# sofi_v7_main.net
KiCad netlist of a schematic drawn in EAGLE
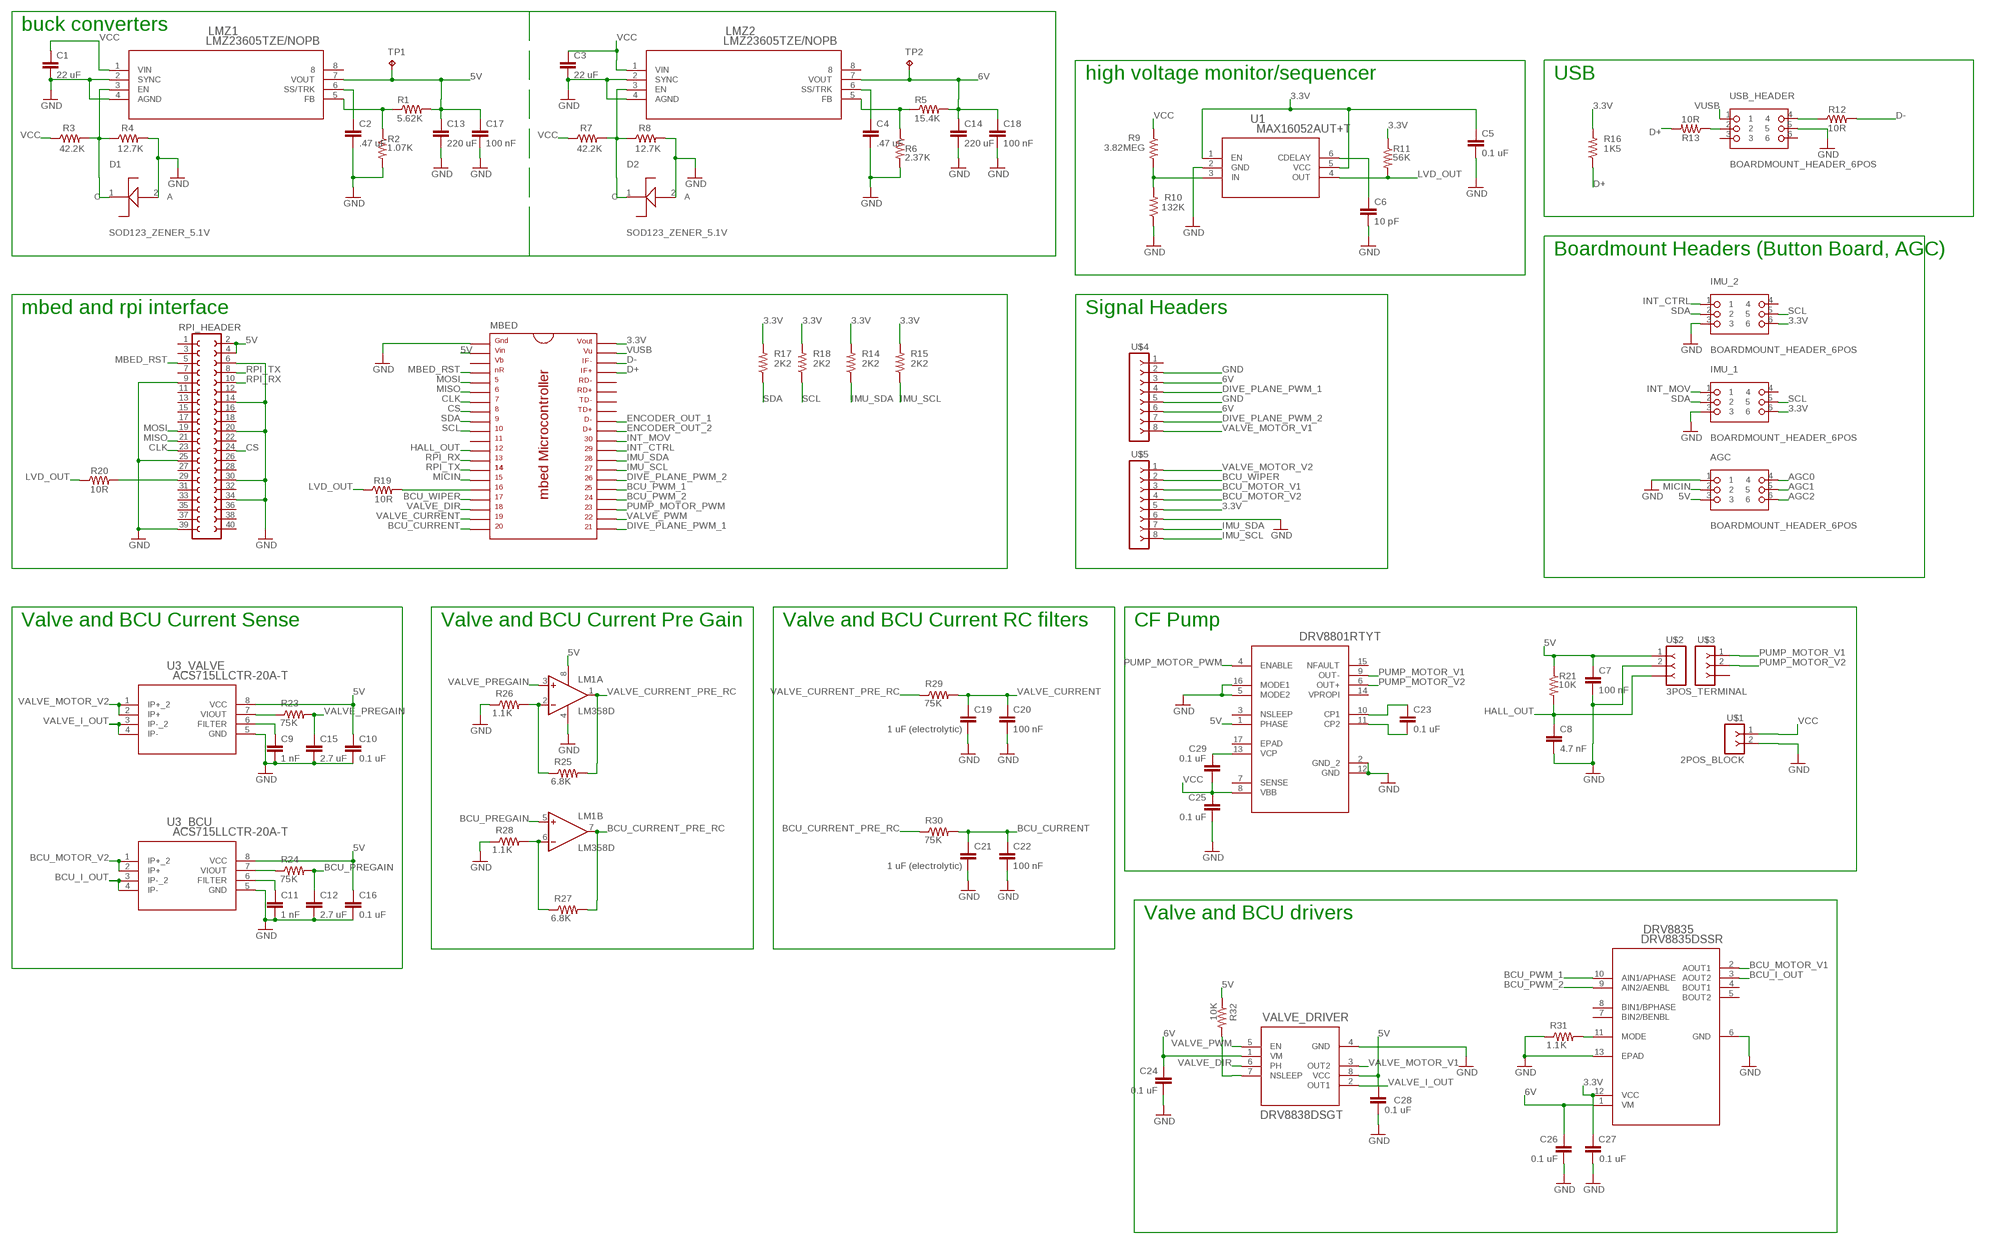
[diagram p0: schematic, sheet 1]

(export (version "E")
  (design (tool "Eeschema 10.0.6"))
  (components
    (comp (ref "AGC")
      (value "BOARDMOUNT_HEADER_6POS")
      (footprint "eagle-import:BOARDMOUNT_HEADER")
      (libsource (lib "eagle-import") (part "BOARDMOUNT_HEADER_6POS"))
    )
    (comp (ref "C1")
      (value "22 uF")
      (footprint "eagle-import:C0805")
      (libsource (lib "eagle-import") (part "C-EUC0805"))
    )
    (comp (ref "C2")
      (value ".47 uF")
      (footprint "eagle-import:C0805")
      (libsource (lib "eagle-import") (part "C-EUC0805"))
    )
    (comp (ref "C3")
      (value "22 uF")
      (footprint "eagle-import:C0805")
      (libsource (lib "eagle-import") (part "C-EUC0805"))
    )
    (comp (ref "C4")
      (value ".47 uF")
      (footprint "eagle-import:C0805")
      (libsource (lib "eagle-import") (part "C-EUC0805"))
    )
    (comp (ref "C5")
      (value "0.1 uF")
      (footprint "eagle-import:C0805")
      (libsource (lib "eagle-import") (part "C-EUC0805"))
    )
    (comp (ref "C6")
      (value "10 pF")
      (footprint "eagle-import:C0603")
      (libsource (lib "eagle-import") (part "C-EUC0603"))
    )
    (comp (ref "C7")
      (value "100 nF")
      (footprint "eagle-import:C0805")
      (libsource (lib "eagle-import") (part "C-EUC0805"))
    )
    (comp (ref "C8")
      (value "4.7 nF")
      (footprint "eagle-import:C0805")
      (libsource (lib "eagle-import") (part "C-EUC0805"))
    )
    (comp (ref "C9")
      (value "1 nF")
      (footprint "eagle-import:C0603")
      (libsource (lib "eagle-import") (part "C-EUC0603"))
    )
    (comp (ref "C10")
      (value "0.1 uF")
      (footprint "eagle-import:C0603")
      (libsource (lib "eagle-import") (part "C-EUC0603"))
    )
    (comp (ref "C11")
      (value "1 nF")
      (footprint "eagle-import:C0603")
      (libsource (lib "eagle-import") (part "C-EUC0603"))
    )
    (comp (ref "C12")
      (value "2.7 uF")
      (footprint "eagle-import:C0603")
      (libsource (lib "eagle-import") (part "C-EUC0603"))
    )
    (comp (ref "C13")
      (value "220 uF")
      (footprint "eagle-import:C1206")
      (libsource (lib "eagle-import") (part "resistor_348_C-EUC1206"))
    )
    (comp (ref "C14")
      (value "220 uF")
      (footprint "eagle-import:C1206")
      (libsource (lib "eagle-import") (part "resistor_348_C-EUC1206"))
    )
    (comp (ref "C15")
      (value "2.7 uF")
      (footprint "eagle-import:C0603")
      (libsource (lib "eagle-import") (part "C-EUC0603"))
    )
    (comp (ref "C16")
      (value "0.1 uF")
      (footprint "eagle-import:C0603")
      (libsource (lib "eagle-import") (part "C-EUC0603"))
    )
    (comp (ref "C17")
      (value "100 nF")
      (footprint "eagle-import:C0805")
      (libsource (lib "eagle-import") (part "C-EUC0805"))
    )
    (comp (ref "C18")
      (value "100 nF")
      (footprint "eagle-import:C0805")
      (libsource (lib "eagle-import") (part "C-EUC0805"))
    )
    (comp (ref "C19")
      (value "1 uF (electrolytic)")
      (footprint "eagle-import:C0603")
      (libsource (lib "eagle-import") (part "C-EUC0603"))
    )
    (comp (ref "C20")
      (value "100 nF")
      (footprint "eagle-import:C0805")
      (libsource (lib "eagle-import") (part "C-EUC0805"))
    )
    (comp (ref "C21")
      (value "1 uF (electrolytic)")
      (footprint "eagle-import:C0603")
      (libsource (lib "eagle-import") (part "C-EUC0603"))
    )
    (comp (ref "C22")
      (value "100 nF")
      (footprint "eagle-import:C0805")
      (libsource (lib "eagle-import") (part "C-EUC0805"))
    )
    (comp (ref "C23")
      (value "0.1 uF")
      (footprint "eagle-import:C0805")
      (libsource (lib "eagle-import") (part "C-EUC0805"))
    )
    (comp (ref "C24")
      (value "0.1 uF")
      (footprint "eagle-import:C0603")
      (libsource (lib "eagle-import") (part "C-EUC0603"))
    )
    (comp (ref "C25")
      (value "0.1 uF")
      (footprint "eagle-import:C0603")
      (libsource (lib "eagle-import") (part "C-EUC0603"))
    )
    (comp (ref "C26")
      (value "0.1 uF")
      (footprint "eagle-import:C0603")
      (libsource (lib "eagle-import") (part "C-EUC0603"))
    )
    (comp (ref "C27")
      (value "0.1 uF")
      (footprint "eagle-import:C0603")
      (libsource (lib "eagle-import") (part "C-EUC0603"))
    )
    (comp (ref "C28")
      (value "0.1 uF")
      (footprint "eagle-import:C0603")
      (libsource (lib "eagle-import") (part "C-EUC0603"))
    )
    (comp (ref "C29")
      (value "0.1 uF")
      (footprint "eagle-import:C0805")
      (libsource (lib "eagle-import") (part "C-EUC0805"))
    )
    (comp (ref "D1")
      (value "SOD123_ZENER_5.1V")
      (footprint "eagle-import:SOD123_ZENER")
      (libsource (lib "eagle-import") (part "SOD123_ZENER_5.1V"))
    )
    (comp (ref "D2")
      (value "SOD123_ZENER_5.1V")
      (footprint "eagle-import:SOD123_ZENER")
      (libsource (lib "eagle-import") (part "SOD123_ZENER_5.1V"))
    )
    (comp (ref "DRV8801")
      (value "DRV8801RTYT")
      (footprint "eagle-import:RTY16")
      (libsource (lib "eagle-import") (part "DRV8801RTYT"))
    )
    (comp (ref "DRV8835")
      (value "DRV8835DSSR")
      (footprint "eagle-import:DSS12_P9X2")
      (libsource (lib "eagle-import") (part "DRV8835DSSR"))
    )
    (comp (ref "IMU_1")
      (value "BOARDMOUNT_HEADER_6POS")
      (footprint "eagle-import:BOARDMOUNT_HEADER")
      (libsource (lib "eagle-import") (part "BOARDMOUNT_HEADER_6POS"))
    )
    (comp (ref "IMU_2")
      (value "BOARDMOUNT_HEADER_6POS")
      (footprint "eagle-import:BOARDMOUNT_HEADER")
      (libsource (lib "eagle-import") (part "BOARDMOUNT_HEADER_6POS"))
    )
    (comp (ref "LM1")
      (value "LM358D")
      (footprint "eagle-import:SO08")
      (libsource (lib "eagle-import") (part "LM358D"))
    )
    (comp (ref "LMZ1")
      (value "LMZ23605TZE/NOPB")
      (footprint "eagle-import:TZA07A")
      (fields (field (name "MANUFACTURER_PART_NUMBER") "LMZ23605TZENOPB"))
      (libsource (lib "eagle-import") (part "LMZ23605TZE/NOPB"))
    )
    (comp (ref "LMZ2")
      (value "LMZ23605TZE/NOPB")
      (footprint "eagle-import:TZA07A")
      (fields (field (name "MANUFACTURER_PART_NUMBER") "LMZ23605TZENOPB"))
      (libsource (lib "eagle-import") (part "LMZ23605TZE/NOPB"))
    )
    (comp (ref "MBED")
      (value "MBED_MICROCONTROLLER")
      (footprint "eagle-import:DIL40_0.9")
      (libsource (lib "eagle-import") (part "MBED_MICROCONTROLLER"))
    )
    (comp (ref "R1")
      (value "5.62K")
      (footprint "eagle-import:M0805")
      (libsource (lib "eagle-import") (part "R-US_M0805"))
    )
    (comp (ref "R2")
      (value "1.07K")
      (footprint "eagle-import:M0805")
      (libsource (lib "eagle-import") (part "R-US_M0805"))
    )
    (comp (ref "R3")
      (value "42.2K")
      (footprint "eagle-import:M0805")
      (libsource (lib "eagle-import") (part "R-US_M0805"))
    )
    (comp (ref "R4")
      (value "12.7K")
      (footprint "eagle-import:M0805")
      (libsource (lib "eagle-import") (part "R-US_M0805"))
    )
    (comp (ref "R5")
      (value "15.4K")
      (footprint "eagle-import:M0805")
      (libsource (lib "eagle-import") (part "R-US_M0805"))
    )
    (comp (ref "R6")
      (value "2.37K")
      (footprint "eagle-import:M0805")
      (libsource (lib "eagle-import") (part "R-US_M0805"))
    )
    (comp (ref "R7")
      (value "42.2K")
      (footprint "eagle-import:M0805")
      (libsource (lib "eagle-import") (part "R-US_M0805"))
    )
    (comp (ref "R8")
      (value "12.7K")
      (footprint "eagle-import:M0805")
      (libsource (lib "eagle-import") (part "R-US_M0805"))
    )
    (comp (ref "R9")
      (value "3.82MEG")
      (footprint "eagle-import:0603")
      (libsource (lib "eagle-import") (part "RESISTOR0603"))
    )
    (comp (ref "R10")
      (value "132K")
      (footprint "eagle-import:0603")
      (libsource (lib "eagle-import") (part "RESISTOR0603"))
    )
    (comp (ref "R11")
      (value "56K")
      (footprint "eagle-import:R0603")
      (libsource (lib "eagle-import") (part "R-US_R0603"))
    )
    (comp (ref "R12")
      (value "10R")
      (footprint "eagle-import:0603")
      (libsource (lib "eagle-import") (part "RESISTOR0603"))
    )
    (comp (ref "R13")
      (value "10R")
      (footprint "eagle-import:0603")
      (libsource (lib "eagle-import") (part "RESISTOR0603"))
    )
    (comp (ref "R14")
      (value "2K2")
      (footprint "eagle-import:0603")
      (libsource (lib "eagle-import") (part "RESISTOR0603"))
    )
    (comp (ref "R15")
      (value "2K2")
      (footprint "eagle-import:0603")
      (libsource (lib "eagle-import") (part "RESISTOR0603"))
    )
    (comp (ref "R16")
      (value "1K5")
      (footprint "eagle-import:0603")
      (libsource (lib "eagle-import") (part "RESISTOR0603"))
    )
    (comp (ref "R17")
      (value "2K2")
      (footprint "eagle-import:0603")
      (libsource (lib "eagle-import") (part "RESISTOR0603"))
    )
    (comp (ref "R18")
      (value "2K2")
      (footprint "eagle-import:0603")
      (libsource (lib "eagle-import") (part "RESISTOR0603"))
    )
    (comp (ref "R19")
      (value "10R")
      (footprint "eagle-import:0603")
      (libsource (lib "eagle-import") (part "RESISTOR0603"))
    )
    (comp (ref "R20")
      (value "10R")
      (footprint "eagle-import:0603")
      (libsource (lib "eagle-import") (part "RESISTOR0603"))
    )
    (comp (ref "R21")
      (value "10K")
      (footprint "eagle-import:M0805")
      (libsource (lib "eagle-import") (part "R-US_M0805"))
    )
    (comp (ref "R23")
      (value "75K")
      (footprint "eagle-import:M0805")
      (libsource (lib "eagle-import") (part "R-US_M0805"))
    )
    (comp (ref "R24")
      (value "75K")
      (footprint "eagle-import:M0805")
      (libsource (lib "eagle-import") (part "R-US_M0805"))
    )
    (comp (ref "R25")
      (value "6.8K")
      (footprint "eagle-import:M0805")
      (libsource (lib "eagle-import") (part "R-US_M0805"))
    )
    (comp (ref "R26")
      (value "1.1K")
      (footprint "eagle-import:M0805")
      (libsource (lib "eagle-import") (part "R-US_M0805"))
    )
    (comp (ref "R27")
      (value "6.8K")
      (footprint "eagle-import:M0805")
      (libsource (lib "eagle-import") (part "R-US_M0805"))
    )
    (comp (ref "R28")
      (value "1.1K")
      (footprint "eagle-import:M0805")
      (libsource (lib "eagle-import") (part "R-US_M0805"))
    )
    (comp (ref "R29")
      (value "75K")
      (footprint "eagle-import:M0805")
      (libsource (lib "eagle-import") (part "R-US_M0805"))
    )
    (comp (ref "R30")
      (value "75K")
      (footprint "eagle-import:M0805")
      (libsource (lib "eagle-import") (part "R-US_M0805"))
    )
    (comp (ref "R31")
      (value "1.1K")
      (footprint "eagle-import:M0805")
      (libsource (lib "eagle-import") (part "R-US_M0805"))
    )
    (comp (ref "R32")
      (value "10K")
      (footprint "eagle-import:M0805")
      (libsource (lib "eagle-import") (part "R-US_M0805"))
    )
    (comp (ref "RPI_HEADER")
      (value "FE20-2")
      (footprint "eagle-import:FE20-2")
      (libsource (lib "eagle-import") (part "FE20-2"))
    )
    (comp (ref "TP1")
      (value "TPB1,27")
      (footprint "eagle-import:B1,27")
      (libsource (lib "eagle-import") (part "TPB1,27"))
    )
    (comp (ref "TP2")
      (value "TPB1,27")
      (footprint "eagle-import:B1,27")
      (libsource (lib "eagle-import") (part "TPB1,27"))
    )
    (comp (ref "U$1")
      (value "2POS_BLOCK")
      (footprint "eagle-import:2POS_BLOCK")
      (libsource (lib "eagle-import") (part "2POS_BLOCK"))
    )
    (comp (ref "U$2")
      (value "3POS_TERMINAL")
      (footprint "eagle-import:3POS_TERMINAL")
      (libsource (lib "eagle-import") (part "3POS_TERMINAL"))
    )
    (comp (ref "U$3")
      (value "3POS_TERMINAL")
      (footprint "eagle-import:3POS_TERMINAL")
      (libsource (lib "eagle-import") (part "3POS_TERMINAL"))
    )
    (comp (ref "U$4")
      (value "8POS_TERMINAL")
      (footprint "eagle-import:8POS_TERMINAL")
      (libsource (lib "eagle-import") (part "8POS_TERMINAL"))
    )
    (comp (ref "U$5")
      (value "8POS_TERMINAL")
      (footprint "eagle-import:8POS_TERMINAL")
      (libsource (lib "eagle-import") (part "8POS_TERMINAL"))
    )
    (comp (ref "U1")
      (value "MAX16052AUT+T")
      (footprint "eagle-import:21-0058I")
      (fields (field (name "MANUFACTURER_PART_NUMBER") "max16052aut+t"))
      (libsource (lib "eagle-import") (part "MAX16052AUT+T"))
    )
    (comp (ref "U3_BCU")
      (value "ACS715LLCTR-20A-T")
      (footprint "eagle-import:SOIC-8")
      (fields (field (name "MANUFACTURER_PART_NUMBER") "ACS715LLCTR20AT"))
      (libsource (lib "eagle-import") (part "ACS715LLCTR-20A-T"))
    )
    (comp (ref "U3_VALVE")
      (value "ACS715LLCTR-20A-T")
      (footprint "eagle-import:SOIC-8")
      (fields (field (name "MANUFACTURER_PART_NUMBER") "ACS715LLCTR20AT"))
      (libsource (lib "eagle-import") (part "ACS715LLCTR-20A-T"))
    )
    (comp (ref "USB_HEADER")
      (value "BOARDMOUNT_HEADER_6POS")
      (footprint "eagle-import:BOARDMOUNT_HEADER")
      (libsource (lib "eagle-import") (part "BOARDMOUNT_HEADER_6POS"))
    )
    (comp (ref "VALVE_DRIVER")
      (value "DRV8838DSGT")
      (footprint "eagle-import:DSG8_P9X1P6")
      (libsource (lib "eagle-import") (part "DRV8838DSGT"))
    )
  )
  (nets
    (net (code "1") (name "3.3V") (class "Default")
      (node (ref "C27") (pin "1") (pinfunction "1_1") (pintype "passive"))
      (node (ref "C5") (pin "1") (pinfunction "1_1") (pintype "passive"))
      (node (ref "DRV8835") (pin "12") (pinfunction "VCC_12") (pintype "power_in"))
      (node (ref "IMU_1") (pin "6") (pinfunction "6_6") (pintype "bidirectional"))
      (node (ref "IMU_2") (pin "6") (pinfunction "6_6") (pintype "bidirectional"))
      (node (ref "MBED") (pin "40") (pinfunction "P$40_40") (pintype "bidirectional"))
      (node (ref "R11") (pin "1") (pinfunction "1_1") (pintype "passive"))
      (node (ref "R14") (pin "2") (pinfunction "2_2") (pintype "passive"))
      (node (ref "R15") (pin "2") (pinfunction "2_2") (pintype "passive"))
      (node (ref "R16") (pin "2") (pinfunction "2_2") (pintype "passive"))
      (node (ref "R17") (pin "2") (pinfunction "2_2") (pintype "passive"))
      (node (ref "R18") (pin "2") (pinfunction "2_2") (pintype "passive"))
      (node (ref "U$5") (pin "5") (pinfunction "5_5") (pintype "passive"))
      (node (ref "U1") (pin "1") (pinfunction "EN_1") (pintype "input"))
      (node (ref "U1") (pin "5") (pinfunction "VCC_5") (pintype "power_in"))
    )
    (net (code "2") (name "5V") (class "Default")
      (node (ref "AGC") (pin "3") (pinfunction "3_3") (pintype "bidirectional"))
      (node (ref "C10") (pin "1") (pinfunction "1_1") (pintype "passive"))
      (node (ref "C13") (pin "1") (pinfunction "1_1") (pintype "passive"))
      (node (ref "C16") (pin "1") (pinfunction "1_1") (pintype "passive"))
      (node (ref "C17") (pin "1") (pinfunction "1_1") (pintype "passive"))
      (node (ref "C28") (pin "1") (pinfunction "1_1") (pintype "passive"))
      (node (ref "C7") (pin "1") (pinfunction "1_1") (pintype "passive"))
      (node (ref "DRV8801") (pin "1") (pinfunction "PHASE_1") (pintype "input"))
      (node (ref "LM1") (pin "8") (pinfunction "V+_8") (pintype "power_in"))
      (node (ref "LMZ1") (pin "7") (pinfunction "VOUT_7") (pintype "output"))
      (node (ref "MBED") (pin "2") (pinfunction "P$2_2") (pintype "bidirectional"))
      (node (ref "R1") (pin "2") (pinfunction "2_2") (pintype "passive"))
      (node (ref "R21") (pin "1") (pinfunction "1_1") (pintype "passive"))
      (node (ref "R32") (pin "1") (pinfunction "1_1") (pintype "passive"))
      (node (ref "RPI_HEADER") (pin "2") (pinfunction "2_2") (pintype "passive"))
      (node (ref "RPI_HEADER") (pin "4") (pinfunction "4_4") (pintype "passive"))
      (node (ref "TP1") (pin "TP") (pinfunction "TP_TP") (pintype "input"))
      (node (ref "U$2") (pin "1") (pinfunction "1_1") (pintype "passive"))
      (node (ref "U3_BCU") (pin "8") (pinfunction "VCC_8") (pintype "power_in"))
      (node (ref "U3_VALVE") (pin "8") (pinfunction "VCC_8") (pintype "power_in"))
      (node (ref "VALVE_DRIVER") (pin "8") (pinfunction "VCC_8") (pintype "power_in"))
    )
    (net (code "3") (name "6V") (class "Default")
      (node (ref "C14") (pin "1") (pinfunction "1_1") (pintype "passive"))
      (node (ref "C18") (pin "1") (pinfunction "1_1") (pintype "passive"))
      (node (ref "C24") (pin "1") (pinfunction "1_1") (pintype "passive"))
      (node (ref "C26") (pin "1") (pinfunction "1_1") (pintype "passive"))
      (node (ref "DRV8835") (pin "1") (pinfunction "VM_1") (pintype "power_in"))
      (node (ref "LMZ2") (pin "7") (pinfunction "VOUT_7") (pintype "output"))
      (node (ref "R5") (pin "2") (pinfunction "2_2") (pintype "passive"))
      (node (ref "TP2") (pin "TP") (pinfunction "TP_TP") (pintype "input"))
      (node (ref "U$4") (pin "3") (pinfunction "3_3") (pintype "passive"))
      (node (ref "U$4") (pin "6") (pinfunction "6_6") (pintype "passive"))
      (node (ref "VALVE_DRIVER") (pin "1") (pinfunction "VM_1") (pintype "power_in"))
    )
    (net (code "4") (name "AGC0") (class "Default")
      (node (ref "AGC") (pin "4") (pinfunction "4_4") (pintype "bidirectional"))
    )
    (net (code "5") (name "AGC1") (class "Default")
      (node (ref "AGC") (pin "5") (pinfunction "5_5") (pintype "bidirectional"))
    )
    (net (code "6") (name "AGC2") (class "Default")
      (node (ref "AGC") (pin "6") (pinfunction "6_6") (pintype "bidirectional"))
    )
    (net (code "7") (name "BCU_CURRENT") (class "Default")
      (node (ref "C21") (pin "1") (pinfunction "1_1") (pintype "passive"))
      (node (ref "C22") (pin "1") (pinfunction "1_1") (pintype "passive"))
      (node (ref "MBED") (pin "20") (pinfunction "P$20_20") (pintype "bidirectional"))
      (node (ref "R30") (pin "2") (pinfunction "2_2") (pintype "passive"))
    )
    (net (code "8") (name "BCU_CURRENT_PRE_RC") (class "Default")
      (node (ref "LM1") (pin "7") (pinfunction "OUT_7") (pintype "output"))
      (node (ref "R27") (pin "2") (pinfunction "2_2") (pintype "passive"))
      (node (ref "R30") (pin "1") (pinfunction "1_1") (pintype "passive"))
    )
    (net (code "9") (name "BCU_I_OUT") (class "Default")
      (node (ref "DRV8835") (pin "3") (pinfunction "AOUT2_3") (pintype "output"))
      (node (ref "U3_BCU") (pin "3") (pinfunction "IP-_2_3") (pintype "output"))
      (node (ref "U3_BCU") (pin "4") (pinfunction "IP-_4") (pintype "output"))
    )
    (net (code "10") (name "BCU_MOTOR_V1") (class "Default")
      (node (ref "DRV8835") (pin "2") (pinfunction "AOUT1_2") (pintype "output"))
      (node (ref "U$5") (pin "3") (pinfunction "3_3") (pintype "passive"))
    )
    (net (code "11") (name "BCU_MOTOR_V2") (class "Default")
      (node (ref "U$5") (pin "4") (pinfunction "4_4") (pintype "passive"))
      (node (ref "U3_BCU") (pin "1") (pinfunction "IP+_2_1") (pintype "input"))
      (node (ref "U3_BCU") (pin "2") (pinfunction "IP+_2") (pintype "input"))
    )
    (net (code "12") (name "BCU_PREGAIN") (class "Default")
      (node (ref "C12") (pin "1") (pinfunction "1_1") (pintype "passive"))
      (node (ref "LM1") (pin "5") (pinfunction "+IN_5") (pintype "input"))
      (node (ref "R24") (pin "2") (pinfunction "2_2") (pintype "passive"))
    )
    (net (code "13") (name "BCU_PWM_1") (class "Default")
      (node (ref "DRV8835") (pin "10") (pinfunction "AIN1/APHASE_10") (pintype "input"))
      (node (ref "MBED") (pin "25") (pinfunction "P$25_25") (pintype "bidirectional"))
    )
    (net (code "14") (name "BCU_PWM_2") (class "Default")
      (node (ref "DRV8835") (pin "9") (pinfunction "AIN2/AENBL_9") (pintype "input"))
      (node (ref "MBED") (pin "24") (pinfunction "P$24_24") (pintype "bidirectional"))
    )
    (net (code "15") (name "BCU_WIPER") (class "Default")
      (node (ref "MBED") (pin "17") (pinfunction "P$17_17") (pintype "bidirectional"))
      (node (ref "U$5") (pin "2") (pinfunction "2_2") (pintype "passive"))
    )
    (net (code "16") (name "CLK") (class "Default")
      (node (ref "MBED") (pin "7") (pinfunction "P$7_7") (pintype "bidirectional"))
      (node (ref "RPI_HEADER") (pin "23") (pinfunction "23_23") (pintype "passive"))
    )
    (net (code "17") (name "CS") (class "Default")
      (node (ref "MBED") (pin "8") (pinfunction "P$8_8") (pintype "bidirectional"))
      (node (ref "RPI_HEADER") (pin "24") (pinfunction "24_24") (pintype "passive"))
    )
    (net (code "18") (name "D+") (class "Default")
      (node (ref "MBED") (pin "37") (pinfunction "P$37_37") (pintype "bidirectional"))
      (node (ref "R13") (pin "2") (pinfunction "2_2") (pintype "passive"))
      (node (ref "R16") (pin "1") (pinfunction "1_1") (pintype "passive"))
    )
    (net (code "19") (name "D-") (class "Default")
      (node (ref "MBED") (pin "38") (pinfunction "P$38_38") (pintype "bidirectional"))
      (node (ref "R12") (pin "2") (pinfunction "2_2") (pintype "passive"))
    )
    (net (code "20") (name "DIVE_PLANE_PWM_1") (class "Default")
      (node (ref "MBED") (pin "21") (pinfunction "P$21_21") (pintype "bidirectional"))
      (node (ref "U$4") (pin "4") (pinfunction "4_4") (pintype "passive"))
    )
    (net (code "21") (name "DIVE_PLANE_PWM_2") (class "Default")
      (node (ref "MBED") (pin "26") (pinfunction "P$26_26") (pintype "bidirectional"))
      (node (ref "U$4") (pin "7") (pinfunction "7_7") (pintype "passive"))
    )
    (net (code "22") (name "ENCODER_OUT_1") (class "Default")
      (node (ref "MBED") (pin "32") (pinfunction "P$32_32") (pintype "bidirectional"))
    )
    (net (code "23") (name "ENCODER_OUT_2") (class "Default")
      (node (ref "MBED") (pin "31") (pinfunction "P$31_31") (pintype "bidirectional"))
    )
    (net (code "24") (name "GND") (class "Default")
      (node (ref "AGC") (pin "1") (pinfunction "1_1") (pintype "bidirectional"))
      (node (ref "C1") (pin "2") (pinfunction "2_2") (pintype "passive"))
      (node (ref "C10") (pin "2") (pinfunction "2_2") (pintype "passive"))
      (node (ref "C11") (pin "2") (pinfunction "2_2") (pintype "passive"))
      (node (ref "C12") (pin "2") (pinfunction "2_2") (pintype "passive"))
      (node (ref "C13") (pin "2") (pinfunction "2_2") (pintype "passive"))
      (node (ref "C14") (pin "2") (pinfunction "2_2") (pintype "passive"))
      (node (ref "C15") (pin "2") (pinfunction "2_2") (pintype "passive"))
      (node (ref "C16") (pin "2") (pinfunction "2_2") (pintype "passive"))
      (node (ref "C17") (pin "2") (pinfunction "2_2") (pintype "passive"))
      (node (ref "C18") (pin "2") (pinfunction "2_2") (pintype "passive"))
      (node (ref "C19") (pin "2") (pinfunction "2_2") (pintype "passive"))
      (node (ref "C2") (pin "2") (pinfunction "2_2") (pintype "passive"))
      (node (ref "C20") (pin "2") (pinfunction "2_2") (pintype "passive"))
      (node (ref "C21") (pin "2") (pinfunction "2_2") (pintype "passive"))
      (node (ref "C22") (pin "2") (pinfunction "2_2") (pintype "passive"))
      (node (ref "C24") (pin "2") (pinfunction "2_2") (pintype "passive"))
      (node (ref "C25") (pin "2") (pinfunction "2_2") (pintype "passive"))
      (node (ref "C26") (pin "2") (pinfunction "2_2") (pintype "passive"))
      (node (ref "C27") (pin "2") (pinfunction "2_2") (pintype "passive"))
      (node (ref "C28") (pin "2") (pinfunction "2_2") (pintype "passive"))
      (node (ref "C3") (pin "2") (pinfunction "2_2") (pintype "passive"))
      (node (ref "C4") (pin "2") (pinfunction "2_2") (pintype "passive"))
      (node (ref "C5") (pin "2") (pinfunction "2_2") (pintype "passive"))
      (node (ref "C6") (pin "2") (pinfunction "2_2") (pintype "passive"))
      (node (ref "C7") (pin "2") (pinfunction "2_2") (pintype "passive"))
      (node (ref "C8") (pin "2") (pinfunction "2_2") (pintype "passive"))
      (node (ref "C9") (pin "2") (pinfunction "2_2") (pintype "passive"))
      (node (ref "D1") (pin "2") (pinfunction "A_2") (pintype "bidirectional"))
      (node (ref "D2") (pin "2") (pinfunction "A_2") (pintype "bidirectional"))
      (node (ref "DRV8801") (pin "12") (pinfunction "GND_12") (pintype "power_in"))
      (node (ref "DRV8801") (pin "16") (pinfunction "MODE1_16") (pintype "input"))
      (node (ref "DRV8801") (pin "2") (pinfunction "GND_2_2") (pintype "power_in"))
      (node (ref "DRV8801") (pin "5") (pinfunction "MODE2_5") (pintype "input"))
      (node (ref "DRV8835") (pin "13") (pinfunction "EPAD_13") (pintype "passive"))
      (node (ref "DRV8835") (pin "6") (pinfunction "GND_6") (pintype "power_in"))
      (node (ref "IMU_1") (pin "3") (pinfunction "3_3") (pintype "bidirectional"))
      (node (ref "IMU_2") (pin "3") (pinfunction "3_3") (pintype "bidirectional"))
      (node (ref "LM1") (pin "4") (pinfunction "V-_4") (pintype "power_in"))
      (node (ref "LMZ1") (pin "2") (pinfunction "SYNC_2") (pintype "input"))
      (node (ref "LMZ1") (pin "4") (pinfunction "AGND_4") (pintype "power_in"))
      (node (ref "LMZ2") (pin "2") (pinfunction "SYNC_2") (pintype "input"))
      (node (ref "LMZ2") (pin "4") (pinfunction "AGND_4") (pintype "power_in"))
      (node (ref "MBED") (pin "1") (pinfunction "P$1_1") (pintype "bidirectional"))
      (node (ref "R10") (pin "1") (pinfunction "1_1") (pintype "passive"))
      (node (ref "R2") (pin "2") (pinfunction "2_2") (pintype "passive"))
      (node (ref "R26") (pin "1") (pinfunction "1_1") (pintype "passive"))
      (node (ref "R28") (pin "1") (pinfunction "1_1") (pintype "passive"))
      (node (ref "R31") (pin "1") (pinfunction "1_1") (pintype "passive"))
      (node (ref "R4") (pin "2") (pinfunction "2_2") (pintype "passive"))
      (node (ref "R6") (pin "2") (pinfunction "2_2") (pintype "passive"))
      (node (ref "R8") (pin "2") (pinfunction "2_2") (pintype "passive"))
      (node (ref "RPI_HEADER") (pin "14") (pinfunction "14_14") (pintype "passive"))
      (node (ref "RPI_HEADER") (pin "20") (pinfunction "20_20") (pintype "passive"))
      (node (ref "RPI_HEADER") (pin "25") (pinfunction "25_25") (pintype "passive"))
      (node (ref "RPI_HEADER") (pin "30") (pinfunction "30_30") (pintype "passive"))
      (node (ref "RPI_HEADER") (pin "34") (pinfunction "34_34") (pintype "passive"))
      (node (ref "RPI_HEADER") (pin "39") (pinfunction "39_39") (pintype "passive"))
      (node (ref "RPI_HEADER") (pin "6") (pinfunction "6_6") (pintype "passive"))
      (node (ref "RPI_HEADER") (pin "9") (pinfunction "9_9") (pintype "passive"))
      (node (ref "U$1") (pin "2") (pinfunction "2_2") (pintype "passive"))
      (node (ref "U$2") (pin "2") (pinfunction "2_2") (pintype "passive"))
      (node (ref "U$4") (pin "2") (pinfunction "2_2") (pintype "passive"))
      (node (ref "U$4") (pin "5") (pinfunction "5_5") (pintype "passive"))
      (node (ref "U$5") (pin "6") (pinfunction "6_6") (pintype "passive"))
      (node (ref "U1") (pin "2") (pinfunction "GND_2") (pintype "power_in"))
      (node (ref "U3_BCU") (pin "5") (pinfunction "GND_5") (pintype "power_in"))
      (node (ref "U3_VALVE") (pin "5") (pinfunction "GND_5") (pintype "power_in"))
      (node (ref "USB_HEADER") (pin "5") (pinfunction "5_5") (pintype "bidirectional"))
      (node (ref "VALVE_DRIVER") (pin "4") (pinfunction "GND_4") (pintype "power_in"))
    )
    (net (code "25") (name "HALL_OUT") (class "Default")
      (node (ref "C8") (pin "1") (pinfunction "1_1") (pintype "passive"))
      (node (ref "MBED") (pin "12") (pinfunction "P$12_12") (pintype "bidirectional"))
      (node (ref "R21") (pin "2") (pinfunction "2_2") (pintype "passive"))
      (node (ref "U$2") (pin "3") (pinfunction "3_3") (pintype "passive"))
    )
    (net (code "26") (name "IMU_SCL") (class "Default")
      (node (ref "MBED") (pin "27") (pinfunction "P$27_27") (pintype "bidirectional"))
      (node (ref "R15") (pin "1") (pinfunction "1_1") (pintype "passive"))
      (node (ref "U$5") (pin "8") (pinfunction "8_8") (pintype "passive"))
    )
    (net (code "27") (name "IMU_SDA") (class "Default")
      (node (ref "MBED") (pin "28") (pinfunction "P$28_28") (pintype "bidirectional"))
      (node (ref "R14") (pin "1") (pinfunction "1_1") (pintype "passive"))
      (node (ref "U$5") (pin "7") (pinfunction "7_7") (pintype "passive"))
    )
    (net (code "28") (name "INT_CTRL") (class "Default")
      (node (ref "IMU_2") (pin "1") (pinfunction "1_1") (pintype "bidirectional"))
      (node (ref "MBED") (pin "29") (pinfunction "P$29_29") (pintype "bidirectional"))
    )
    (net (code "29") (name "INT_MOV") (class "Default")
      (node (ref "IMU_1") (pin "1") (pinfunction "1_1") (pintype "bidirectional"))
      (node (ref "MBED") (pin "30") (pinfunction "P$30_30") (pintype "bidirectional"))
    )
    (net (code "30") (name "LVD_OUT") (class "Default")
      (node (ref "R11") (pin "2") (pinfunction "2_2") (pintype "passive"))
      (node (ref "R19") (pin "1") (pinfunction "1_1") (pintype "passive"))
      (node (ref "R20") (pin "1") (pinfunction "1_1") (pintype "passive"))
      (node (ref "U1") (pin "4") (pinfunction "OUT_4") (pintype "output"))
    )
    (net (code "31") (name "MBED_RST") (class "Default")
      (node (ref "MBED") (pin "4") (pinfunction "P$4_4") (pintype "bidirectional"))
      (node (ref "RPI_HEADER") (pin "5") (pinfunction "5_5") (pintype "passive"))
    )
    (net (code "32") (name "MICIN") (class "Default")
      (node (ref "AGC") (pin "2") (pinfunction "2_2") (pintype "bidirectional"))
      (node (ref "MBED") (pin "15") (pinfunction "P$15_15") (pintype "bidirectional"))
    )
    (net (code "33") (name "MISO") (class "Default")
      (node (ref "MBED") (pin "6") (pinfunction "P$6_6") (pintype "bidirectional"))
      (node (ref "RPI_HEADER") (pin "21") (pinfunction "21_21") (pintype "passive"))
    )
    (net (code "34") (name "MOSI") (class "Default")
      (node (ref "MBED") (pin "5") (pinfunction "P$5_5") (pintype "bidirectional"))
      (node (ref "RPI_HEADER") (pin "19") (pinfunction "19_19") (pintype "passive"))
    )
    (net (code "35") (name "Net-(D1-C)") (class "Default")
      (node (ref "D1") (pin "1") (pinfunction "C_1") (pintype "bidirectional"))
      (node (ref "LMZ1") (pin "3") (pinfunction "EN_3") (pintype "input"))
      (node (ref "R3") (pin "2") (pinfunction "2_2") (pintype "passive"))
      (node (ref "R4") (pin "1") (pinfunction "1_1") (pintype "passive"))
    )
    (net (code "36") (name "Net-(D2-C)") (class "Default")
      (node (ref "D2") (pin "1") (pinfunction "C_1") (pintype "bidirectional"))
      (node (ref "LMZ2") (pin "3") (pinfunction "EN_3") (pintype "input"))
      (node (ref "R7") (pin "2") (pinfunction "2_2") (pintype "passive"))
      (node (ref "R8") (pin "1") (pinfunction "1_1") (pintype "passive"))
    )
    (net (code "37") (name "Net-(DRV8801-CP1)") (class "Default")
      (node (ref "C23") (pin "1") (pinfunction "1_1") (pintype "passive"))
      (node (ref "DRV8801") (pin "10") (pinfunction "CP1_10") (pintype "passive"))
    )
    (net (code "38") (name "Net-(DRV8801-CP2)") (class "Default")
      (node (ref "C23") (pin "2") (pinfunction "2_2") (pintype "passive"))
      (node (ref "DRV8801") (pin "11") (pinfunction "CP2_11") (pintype "passive"))
    )
    (net (code "39") (name "Net-(DRV8801-VCP)") (class "Default")
      (node (ref "C29") (pin "1") (pinfunction "1_1") (pintype "passive"))
      (node (ref "DRV8801") (pin "13") (pinfunction "VCP_13") (pintype "passive"))
    )
    (net (code "40") (name "Net-(DRV8835-MODE)") (class "Default")
      (node (ref "DRV8835") (pin "11") (pinfunction "MODE_11") (pintype "input"))
      (node (ref "R31") (pin "2") (pinfunction "2_2") (pintype "passive"))
    )
    (net (code "41") (name "Net-(LM1A--IN)") (class "Default")
      (node (ref "LM1") (pin "2") (pinfunction "-IN_2") (pintype "input"))
      (node (ref "R25") (pin "1") (pinfunction "1_1") (pintype "passive"))
      (node (ref "R26") (pin "2") (pinfunction "2_2") (pintype "passive"))
    )
    (net (code "42") (name "Net-(LM1B--IN)") (class "Default")
      (node (ref "LM1") (pin "6") (pinfunction "-IN_6") (pintype "input"))
      (node (ref "R27") (pin "1") (pinfunction "1_1") (pintype "passive"))
      (node (ref "R28") (pin "2") (pinfunction "2_2") (pintype "passive"))
    )
    (net (code "43") (name "Net-(LMZ1-FB)") (class "Default")
      (node (ref "LMZ1") (pin "5") (pinfunction "FB_5") (pintype "input"))
      (node (ref "R1") (pin "1") (pinfunction "1_1") (pintype "passive"))
      (node (ref "R2") (pin "1") (pinfunction "1_1") (pintype "passive"))
    )
    (net (code "44") (name "Net-(LMZ1-SS{slash}TRK)") (class "Default")
      (node (ref "C2") (pin "1") (pinfunction "1_1") (pintype "passive"))
      (node (ref "LMZ1") (pin "6") (pinfunction "SS/TRK_6") (pintype "bidirectional"))
    )
    (net (code "45") (name "Net-(LMZ2-FB)") (class "Default")
      (node (ref "LMZ2") (pin "5") (pinfunction "FB_5") (pintype "input"))
      (node (ref "R5") (pin "1") (pinfunction "1_1") (pintype "passive"))
      (node (ref "R6") (pin "1") (pinfunction "1_1") (pintype "passive"))
    )
    (net (code "46") (name "Net-(LMZ2-SS{slash}TRK)") (class "Default")
      (node (ref "C4") (pin "1") (pinfunction "1_1") (pintype "passive"))
      (node (ref "LMZ2") (pin "6") (pinfunction "SS/TRK_6") (pintype "bidirectional"))
    )
    (net (code "47") (name "Net-(MBED-P$16)") (class "Default")
      (node (ref "MBED") (pin "16") (pinfunction "P$16_16") (pintype "bidirectional"))
      (node (ref "R19") (pin "2") (pinfunction "2_2") (pintype "passive"))
    )
    (net (code "48") (name "Net-(R12-Pad1)") (class "Default")
      (node (ref "R12") (pin "1") (pinfunction "1_1") (pintype "passive"))
      (node (ref "USB_HEADER") (pin "4") (pinfunction "4_4") (pintype "bidirectional"))
    )
    (net (code "49") (name "Net-(R13-Pad1)") (class "Default")
      (node (ref "R13") (pin "1") (pinfunction "1_1") (pintype "passive"))
      (node (ref "USB_HEADER") (pin "2") (pinfunction "2_2") (pintype "bidirectional"))
    )
    (net (code "50") (name "Net-(R20-Pad2)") (class "Default")
      (node (ref "R20") (pin "2") (pinfunction "2_2") (pintype "passive"))
      (node (ref "RPI_HEADER") (pin "29") (pinfunction "29_29") (pintype "passive"))
    )
    (net (code "51") (name "Net-(U1-CDELAY)") (class "Default")
      (node (ref "C6") (pin "1") (pinfunction "1_1") (pintype "passive"))
      (node (ref "U1") (pin "6") (pinfunction "CDELAY_6") (pintype "input"))
    )
    (net (code "52") (name "Net-(U1-IN)") (class "Default")
      (node (ref "R10") (pin "2") (pinfunction "2_2") (pintype "passive"))
      (node (ref "R9") (pin "2") (pinfunction "2_2") (pintype "passive"))
      (node (ref "U1") (pin "3") (pinfunction "IN_3") (pintype "input"))
    )
    (net (code "53") (name "Net-(U3_BCU-FILTER)") (class "Default")
      (node (ref "C11") (pin "1") (pinfunction "1_1") (pintype "passive"))
      (node (ref "U3_BCU") (pin "6") (pinfunction "FILTER_6") (pintype "passive"))
    )
    (net (code "54") (name "Net-(U3_BCU-VIOUT)") (class "Default")
      (node (ref "R24") (pin "1") (pinfunction "1_1") (pintype "passive"))
      (node (ref "U3_BCU") (pin "7") (pinfunction "VIOUT_7") (pintype "output"))
    )
    (net (code "55") (name "Net-(U3_VALVE-FILTER)") (class "Default")
      (node (ref "C9") (pin "1") (pinfunction "1_1") (pintype "passive"))
      (node (ref "U3_VALVE") (pin "6") (pinfunction "FILTER_6") (pintype "passive"))
    )
    (net (code "56") (name "Net-(U3_VALVE-VIOUT)") (class "Default")
      (node (ref "R23") (pin "1") (pinfunction "1_1") (pintype "passive"))
      (node (ref "U3_VALVE") (pin "7") (pinfunction "VIOUT_7") (pintype "output"))
    )
    (net (code "57") (name "Net-(VALVE_DRIVER-NSLEEP)") (class "Default")
      (node (ref "R32") (pin "2") (pinfunction "2_2") (pintype "passive"))
      (node (ref "VALVE_DRIVER") (pin "7") (pinfunction "NSLEEP_7") (pintype "input"))
    )
    (net (code "58") (name "PUMP_MOTOR_PWM") (class "Default")
      (node (ref "DRV8801") (pin "4") (pinfunction "ENABLE_4") (pintype "input"))
      (node (ref "MBED") (pin "23") (pinfunction "P$23_23") (pintype "bidirectional"))
    )
    (net (code "59") (name "PUMP_MOTOR_V1") (class "Default")
      (node (ref "DRV8801") (pin "9") (pinfunction "OUT-_9") (pintype "output"))
      (node (ref "U$3") (pin "1") (pinfunction "1_1") (pintype "passive"))
    )
    (net (code "60") (name "PUMP_MOTOR_V2") (class "Default")
      (node (ref "DRV8801") (pin "6") (pinfunction "OUT+_6") (pintype "output"))
      (node (ref "U$3") (pin "2") (pinfunction "2_2") (pintype "passive"))
    )
    (net (code "61") (name "RPI_RX") (class "Default")
      (node (ref "MBED") (pin "13") (pinfunction "P$13_13") (pintype "bidirectional"))
      (node (ref "RPI_HEADER") (pin "10") (pinfunction "10_10") (pintype "passive"))
    )
    (net (code "62") (name "RPI_TX") (class "Default")
      (node (ref "MBED") (pin "14") (pinfunction "P$14_14") (pintype "bidirectional"))
      (node (ref "RPI_HEADER") (pin "8") (pinfunction "8_8") (pintype "passive"))
    )
    (net (code "63") (name "SCL") (class "Default")
      (node (ref "IMU_1") (pin "5") (pinfunction "5_5") (pintype "bidirectional"))
      (node (ref "IMU_2") (pin "5") (pinfunction "5_5") (pintype "bidirectional"))
      (node (ref "MBED") (pin "10") (pinfunction "P$10_10") (pintype "bidirectional"))
      (node (ref "R18") (pin "1") (pinfunction "1_1") (pintype "passive"))
    )
    (net (code "64") (name "SDA") (class "Default")
      (node (ref "IMU_1") (pin "2") (pinfunction "2_2") (pintype "bidirectional"))
      (node (ref "IMU_2") (pin "2") (pinfunction "2_2") (pintype "bidirectional"))
      (node (ref "MBED") (pin "9") (pinfunction "P$9_9") (pintype "bidirectional"))
      (node (ref "R17") (pin "1") (pinfunction "1_1") (pintype "passive"))
    )
    (net (code "65") (name "SENSE") (class "Default")
      (node (ref "DRV8801") (pin "7") (pinfunction "SENSE_7") (pintype "power_in"))
    )
    (net (code "66") (name "VALVE_CURRENT") (class "Default")
      (node (ref "C19") (pin "1") (pinfunction "1_1") (pintype "passive"))
      (node (ref "C20") (pin "1") (pinfunction "1_1") (pintype "passive"))
      (node (ref "MBED") (pin "19") (pinfunction "P$19_19") (pintype "bidirectional"))
      (node (ref "R29") (pin "2") (pinfunction "2_2") (pintype "passive"))
    )
    (net (code "67") (name "VALVE_CURRENT_PRE_RC") (class "Default")
      (node (ref "LM1") (pin "1") (pinfunction "OUT_1") (pintype "output"))
      (node (ref "R25") (pin "2") (pinfunction "2_2") (pintype "passive"))
      (node (ref "R29") (pin "1") (pinfunction "1_1") (pintype "passive"))
    )
    (net (code "68") (name "VALVE_DIR") (class "Default")
      (node (ref "MBED") (pin "18") (pinfunction "P$18_18") (pintype "bidirectional"))
      (node (ref "VALVE_DRIVER") (pin "6") (pinfunction "PH_6") (pintype "input"))
    )
    (net (code "69") (name "VALVE_I_OUT") (class "Default")
      (node (ref "U3_VALVE") (pin "3") (pinfunction "IP-_2_3") (pintype "output"))
      (node (ref "U3_VALVE") (pin "4") (pinfunction "IP-_4") (pintype "output"))
      (node (ref "VALVE_DRIVER") (pin "2") (pinfunction "OUT1_2") (pintype "output"))
    )
    (net (code "70") (name "VALVE_MOTOR_V1") (class "Default")
      (node (ref "U$4") (pin "8") (pinfunction "8_8") (pintype "passive"))
      (node (ref "VALVE_DRIVER") (pin "3") (pinfunction "OUT2_3") (pintype "output"))
    )
    (net (code "71") (name "VALVE_MOTOR_V2") (class "Default")
      (node (ref "U$5") (pin "1") (pinfunction "1_1") (pintype "passive"))
      (node (ref "U3_VALVE") (pin "1") (pinfunction "IP+_2_1") (pintype "input"))
      (node (ref "U3_VALVE") (pin "2") (pinfunction "IP+_2") (pintype "input"))
    )
    (net (code "72") (name "VALVE_PREGAIN") (class "Default")
      (node (ref "C15") (pin "1") (pinfunction "1_1") (pintype "passive"))
      (node (ref "LM1") (pin "3") (pinfunction "+IN_3") (pintype "input"))
      (node (ref "R23") (pin "2") (pinfunction "2_2") (pintype "passive"))
    )
    (net (code "73") (name "VALVE_PWM") (class "Default")
      (node (ref "MBED") (pin "22") (pinfunction "P$22_22") (pintype "bidirectional"))
      (node (ref "VALVE_DRIVER") (pin "5") (pinfunction "EN_5") (pintype "input"))
    )
    (net (code "74") (name "VCC") (class "Default")
      (node (ref "C1") (pin "1") (pinfunction "1_1") (pintype "passive"))
      (node (ref "C25") (pin "1") (pinfunction "1_1") (pintype "passive"))
      (node (ref "C29") (pin "2") (pinfunction "2_2") (pintype "passive"))
      (node (ref "C3") (pin "1") (pinfunction "1_1") (pintype "passive"))
      (node (ref "DRV8801") (pin "8") (pinfunction "VBB_8") (pintype "power_in"))
      (node (ref "LMZ1") (pin "1") (pinfunction "VIN_1") (pintype "input"))
      (node (ref "LMZ2") (pin "1") (pinfunction "VIN_1") (pintype "input"))
      (node (ref "R3") (pin "1") (pinfunction "1_1") (pintype "passive"))
      (node (ref "R7") (pin "1") (pinfunction "1_1") (pintype "passive"))
      (node (ref "R9") (pin "1") (pinfunction "1_1") (pintype "passive"))
      (node (ref "U$1") (pin "1") (pinfunction "1_1") (pintype "passive"))
    )
    (net (code "75") (name "VUSB") (class "Default")
      (node (ref "MBED") (pin "39") (pinfunction "P$39_39") (pintype "bidirectional"))
      (node (ref "USB_HEADER") (pin "1") (pinfunction "1_1") (pintype "bidirectional"))
    )
    (net (code "76") (name "unconnected-(DRV8801-EPAD-Pad17)") (class "Default")
      (node (ref "DRV8801") (pin "17") (pinfunction "EPAD_17") (pintype "passive"))
    )
    (net (code "77") (name "unconnected-(DRV8801-NFAULT-Pad15)") (class "Default")
      (node (ref "DRV8801") (pin "15") (pinfunction "NFAULT_15") (pintype "output"))
    )
    (net (code "78") (name "unconnected-(DRV8801-NSLEEP-Pad3)") (class "Default")
      (node (ref "DRV8801") (pin "3") (pinfunction "NSLEEP_3") (pintype "input"))
    )
    (net (code "79") (name "unconnected-(DRV8801-VPROPI-Pad14)") (class "Default")
      (node (ref "DRV8801") (pin "14") (pinfunction "VPROPI_14") (pintype "output"))
    )
    (net (code "80") (name "unconnected-(DRV8835-BIN1{slash}BPHASE-Pad8)") (class "Default")
      (node (ref "DRV8835") (pin "8") (pinfunction "BIN1/BPHASE_8") (pintype "input"))
    )
    (net (code "81") (name "unconnected-(DRV8835-BIN2{slash}BENBL-Pad7)") (class "Default")
      (node (ref "DRV8835") (pin "7") (pinfunction "BIN2/BENBL_7") (pintype "input"))
    )
    (net (code "82") (name "unconnected-(DRV8835-BOUT1-Pad4)") (class "Default")
      (node (ref "DRV8835") (pin "4") (pinfunction "BOUT1_4") (pintype "output"))
    )
    (net (code "83") (name "unconnected-(DRV8835-BOUT2-Pad5)") (class "Default")
      (node (ref "DRV8835") (pin "5") (pinfunction "BOUT2_5") (pintype "output"))
    )
    (net (code "84") (name "unconnected-(IMU_1-Pad4)") (class "Default")
      (node (ref "IMU_1") (pin "4") (pinfunction "4_4") (pintype "bidirectional"))
    )
    (net (code "85") (name "unconnected-(IMU_2-Pad4)") (class "Default")
      (node (ref "IMU_2") (pin "4") (pinfunction "4_4") (pintype "bidirectional"))
    )
    (net (code "86") (name "unconnected-(LMZ1-Pad8)") (class "Default")
      (node (ref "LMZ1") (pin "8") (pinfunction "8_8") (pintype "passive"))
    )
    (net (code "87") (name "unconnected-(LMZ2-Pad8)") (class "Default")
      (node (ref "LMZ2") (pin "8") (pinfunction "8_8") (pintype "passive"))
    )
    (net (code "88") (name "unconnected-(MBED-P$3-Pad3)") (class "Default")
      (node (ref "MBED") (pin "3") (pinfunction "P$3_3") (pintype "bidirectional"))
    )
    (net (code "89") (name "unconnected-(MBED-P$11-Pad11)") (class "Default")
      (node (ref "MBED") (pin "11") (pinfunction "P$11_11") (pintype "bidirectional"))
    )
    (net (code "90") (name "unconnected-(MBED-P$33-Pad33)") (class "Default")
      (node (ref "MBED") (pin "33") (pinfunction "P$33_33") (pintype "bidirectional"))
    )
    (net (code "91") (name "unconnected-(MBED-P$34-Pad34)") (class "Default")
      (node (ref "MBED") (pin "34") (pinfunction "P$34_34") (pintype "bidirectional"))
    )
    (net (code "92") (name "unconnected-(MBED-P$35-Pad35)") (class "Default")
      (node (ref "MBED") (pin "35") (pinfunction "P$35_35") (pintype "bidirectional"))
    )
    (net (code "93") (name "unconnected-(MBED-P$36-Pad36)") (class "Default")
      (node (ref "MBED") (pin "36") (pinfunction "P$36_36") (pintype "bidirectional"))
    )
    (net (code "94") (name "unconnected-(RPI_HEADER-Pad1)") (class "Default")
      (node (ref "RPI_HEADER") (pin "1") (pinfunction "1_1") (pintype "passive"))
    )
    (net (code "95") (name "unconnected-(RPI_HEADER-Pad3)") (class "Default")
      (node (ref "RPI_HEADER") (pin "3") (pinfunction "3_3") (pintype "passive"))
    )
    (net (code "96") (name "unconnected-(RPI_HEADER-Pad7)") (class "Default")
      (node (ref "RPI_HEADER") (pin "7") (pinfunction "7_7") (pintype "passive"))
    )
    (net (code "97") (name "unconnected-(RPI_HEADER-Pad11)") (class "Default")
      (node (ref "RPI_HEADER") (pin "11") (pinfunction "11_11") (pintype "passive"))
    )
    (net (code "98") (name "unconnected-(RPI_HEADER-Pad12)") (class "Default")
      (node (ref "RPI_HEADER") (pin "12") (pinfunction "12_12") (pintype "passive"))
    )
    (net (code "99") (name "unconnected-(RPI_HEADER-Pad13)") (class "Default")
      (node (ref "RPI_HEADER") (pin "13") (pinfunction "13_13") (pintype "passive"))
    )
    (net (code "100") (name "unconnected-(RPI_HEADER-Pad15)") (class "Default")
      (node (ref "RPI_HEADER") (pin "15") (pinfunction "15_15") (pintype "passive"))
    )
    (net (code "101") (name "unconnected-(RPI_HEADER-Pad16)") (class "Default")
      (node (ref "RPI_HEADER") (pin "16") (pinfunction "16_16") (pintype "passive"))
    )
    (net (code "102") (name "unconnected-(RPI_HEADER-Pad17)") (class "Default")
      (node (ref "RPI_HEADER") (pin "17") (pinfunction "17_17") (pintype "passive"))
    )
    (net (code "103") (name "unconnected-(RPI_HEADER-Pad18)") (class "Default")
      (node (ref "RPI_HEADER") (pin "18") (pinfunction "18_18") (pintype "passive"))
    )
    (net (code "104") (name "unconnected-(RPI_HEADER-Pad22)") (class "Default")
      (node (ref "RPI_HEADER") (pin "22") (pinfunction "22_22") (pintype "passive"))
    )
    (net (code "105") (name "unconnected-(RPI_HEADER-Pad26)") (class "Default")
      (node (ref "RPI_HEADER") (pin "26") (pinfunction "26_26") (pintype "passive"))
    )
    (net (code "106") (name "unconnected-(RPI_HEADER-Pad27)") (class "Default")
      (node (ref "RPI_HEADER") (pin "27") (pinfunction "27_27") (pintype "passive"))
    )
    (net (code "107") (name "unconnected-(RPI_HEADER-Pad28)") (class "Default")
      (node (ref "RPI_HEADER") (pin "28") (pinfunction "28_28") (pintype "passive"))
    )
    (net (code "108") (name "unconnected-(RPI_HEADER-Pad31)") (class "Default")
      (node (ref "RPI_HEADER") (pin "31") (pinfunction "31_31") (pintype "passive"))
    )
    (net (code "109") (name "unconnected-(RPI_HEADER-Pad32)") (class "Default")
      (node (ref "RPI_HEADER") (pin "32") (pinfunction "32_32") (pintype "passive"))
    )
    (net (code "110") (name "unconnected-(RPI_HEADER-Pad33)") (class "Default")
      (node (ref "RPI_HEADER") (pin "33") (pinfunction "33_33") (pintype "passive"))
    )
    (net (code "111") (name "unconnected-(RPI_HEADER-Pad35)") (class "Default")
      (node (ref "RPI_HEADER") (pin "35") (pinfunction "35_35") (pintype "passive"))
    )
    (net (code "112") (name "unconnected-(RPI_HEADER-Pad36)") (class "Default")
      (node (ref "RPI_HEADER") (pin "36") (pinfunction "36_36") (pintype "passive"))
    )
    (net (code "113") (name "unconnected-(RPI_HEADER-Pad37)") (class "Default")
      (node (ref "RPI_HEADER") (pin "37") (pinfunction "37_37") (pintype "passive"))
    )
    (net (code "114") (name "unconnected-(RPI_HEADER-Pad38)") (class "Default")
      (node (ref "RPI_HEADER") (pin "38") (pinfunction "38_38") (pintype "passive"))
    )
    (net (code "115") (name "unconnected-(RPI_HEADER-Pad40)") (class "Default")
      (node (ref "RPI_HEADER") (pin "40") (pinfunction "40_40") (pintype "passive"))
    )
    (net (code "116") (name "unconnected-(U$3-Pad3)") (class "Default")
      (node (ref "U$3") (pin "3") (pinfunction "3_3") (pintype "passive"))
    )
    (net (code "117") (name "unconnected-(U$4-Pad1)") (class "Default")
      (node (ref "U$4") (pin "1") (pinfunction "1_1") (pintype "passive"))
    )
    (net (code "118") (name "unconnected-(USB_HEADER-Pad3)") (class "Default")
      (node (ref "USB_HEADER") (pin "3") (pinfunction "3_3") (pintype "bidirectional"))
    )
    (net (code "119") (name "unconnected-(USB_HEADER-Pad6)") (class "Default")
      (node (ref "USB_HEADER") (pin "6") (pinfunction "6_6") (pintype "bidirectional"))
    )
  )
)
